# CONNECTEUR_2.net
KiCad netlist of a schematic drawn in Altium Designer
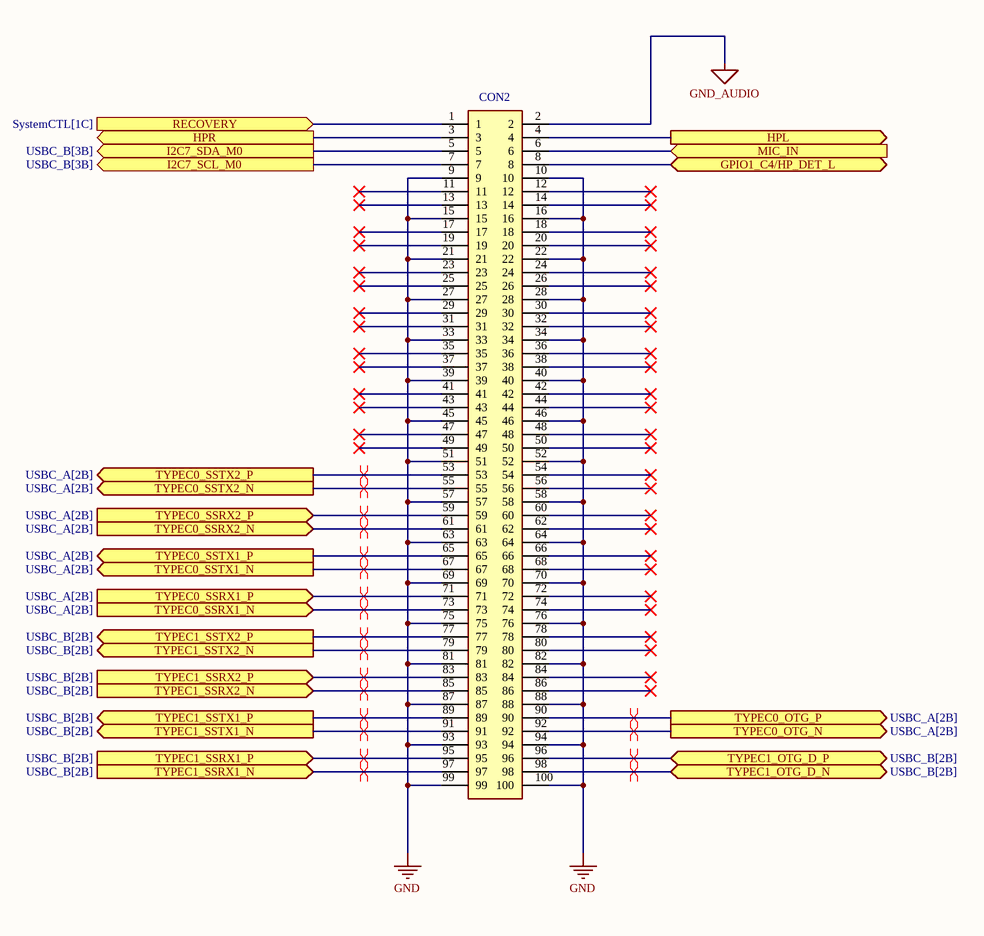
[diagram p0: CONNECTEUR_2.SchDoc, middle]

(export (version "E")
  (design (tool "Eeschema 10.0.6"))
  (components
    (comp (ref "CON2")
      (value "DF40HC")
      (footprint "SamacSys:DF40HC30100DS04V51")
      (description "Stacking Board Connector, DF40 Series, Receptacle, 0.4 mm, 100, Surface Mount, G")
      (fields
        (field (name "MANUFACTURER_PART_NUMBER") "DF40HC(3.0)-100DS-0.4V(51")
        (field (name "MOUSER PART NUMBER") "798-DF40HC30100DS451")
      )
      (libsource (lib "SamacSys") (part "DF40HC(3.0)-100DS-0.4V(51)"))
    )
  )
  (nets
    (net (code "1") (name "/GPIO1_C4{slash}HP_DET_L") (class "Default")
      (node (ref "CON2") (pin "8") (pinfunction "8_8") (pintype "passive"))
    )
    (net (code "2") (name "/HPL") (class "Default")
      (node (ref "CON2") (pin "4") (pinfunction "4_4") (pintype "passive"))
    )
    (net (code "3") (name "/HPR") (class "Default")
      (node (ref "CON2") (pin "3") (pinfunction "3_3") (pintype "passive"))
    )
    (net (code "4") (name "/I2C7_SCL_M0") (class "Default")
      (node (ref "CON2") (pin "7") (pinfunction "7_7") (pintype "passive"))
    )
    (net (code "5") (name "/I2C7_SDA_M0") (class "Default")
      (node (ref "CON2") (pin "5") (pinfunction "5_5") (pintype "passive"))
    )
    (net (code "6") (name "/MIC_IN") (class "Default")
      (node (ref "CON2") (pin "6") (pinfunction "6_6") (pintype "passive"))
    )
    (net (code "7") (name "/RECOVERY") (class "Default")
      (node (ref "CON2") (pin "1") (pinfunction "1_1") (pintype "passive"))
    )
    (net (code "8") (name "/TYPEC0_OTG_N") (class "Default")
      (node (ref "CON2") (pin "92") (pinfunction "92_92") (pintype "passive"))
    )
    (net (code "9") (name "/TYPEC0_OTG_P") (class "Default")
      (node (ref "CON2") (pin "90") (pinfunction "90_90") (pintype "passive"))
    )
    (net (code "10") (name "/TYPEC0_SSRX1_N") (class "Default")
      (node (ref "CON2") (pin "73") (pinfunction "73_73") (pintype "passive"))
    )
    (net (code "11") (name "/TYPEC0_SSRX1_P") (class "Default")
      (node (ref "CON2") (pin "71") (pinfunction "71_71") (pintype "passive"))
    )
    (net (code "12") (name "/TYPEC0_SSRX2_N") (class "Default")
      (node (ref "CON2") (pin "61") (pinfunction "61_61") (pintype "passive"))
    )
    (net (code "13") (name "/TYPEC0_SSRX2_P") (class "Default")
      (node (ref "CON2") (pin "59") (pinfunction "59_59") (pintype "passive"))
    )
    (net (code "14") (name "/TYPEC0_SSTX1_N") (class "Default")
      (node (ref "CON2") (pin "67") (pinfunction "67_67") (pintype "passive"))
    )
    (net (code "15") (name "/TYPEC0_SSTX1_P") (class "Default")
      (node (ref "CON2") (pin "65") (pinfunction "65_65") (pintype "passive"))
    )
    (net (code "16") (name "/TYPEC0_SSTX2_N") (class "Default")
      (node (ref "CON2") (pin "55") (pinfunction "55_55") (pintype "passive"))
    )
    (net (code "17") (name "/TYPEC0_SSTX2_P") (class "Default")
      (node (ref "CON2") (pin "53") (pinfunction "53_53") (pintype "passive"))
    )
    (net (code "18") (name "/TYPEC1_OTG_D_N") (class "Default")
      (node (ref "CON2") (pin "98") (pinfunction "98_98") (pintype "passive"))
    )
    (net (code "19") (name "/TYPEC1_OTG_D_P") (class "Default")
      (node (ref "CON2") (pin "96") (pinfunction "96_96") (pintype "passive"))
    )
    (net (code "20") (name "/TYPEC1_SSRX1_N") (class "Default")
      (node (ref "CON2") (pin "97") (pinfunction "97_97") (pintype "passive"))
    )
    (net (code "21") (name "/TYPEC1_SSRX1_P") (class "Default")
      (node (ref "CON2") (pin "95") (pinfunction "95_95") (pintype "passive"))
    )
    (net (code "22") (name "/TYPEC1_SSRX2_N") (class "Default")
      (node (ref "CON2") (pin "85") (pinfunction "85_85") (pintype "passive"))
    )
    (net (code "23") (name "/TYPEC1_SSRX2_P") (class "Default")
      (node (ref "CON2") (pin "83") (pinfunction "83_83") (pintype "passive"))
    )
    (net (code "24") (name "/TYPEC1_SSTX1_N") (class "Default")
      (node (ref "CON2") (pin "91") (pinfunction "91_91") (pintype "passive"))
    )
    (net (code "25") (name "/TYPEC1_SSTX1_P") (class "Default")
      (node (ref "CON2") (pin "89") (pinfunction "89_89") (pintype "passive"))
    )
    (net (code "26") (name "/TYPEC1_SSTX2_N") (class "Default")
      (node (ref "CON2") (pin "79") (pinfunction "79_79") (pintype "passive"))
    )
    (net (code "27") (name "/TYPEC1_SSTX2_P") (class "Default")
      (node (ref "CON2") (pin "77") (pinfunction "77_77") (pintype "passive"))
    )
    (net (code "28") (name "GND") (class "Default")
      (node (ref "CON2") (pin "10") (pinfunction "10_10") (pintype "passive"))
      (node (ref "CON2") (pin "100") (pinfunction "100_100") (pintype "passive"))
      (node (ref "CON2") (pin "15") (pinfunction "15_15") (pintype "passive"))
      (node (ref "CON2") (pin "16") (pinfunction "16_16") (pintype "passive"))
      (node (ref "CON2") (pin "21") (pinfunction "21_21") (pintype "passive"))
      (node (ref "CON2") (pin "22") (pinfunction "22_22") (pintype "passive"))
      (node (ref "CON2") (pin "27") (pinfunction "27_27") (pintype "passive"))
      (node (ref "CON2") (pin "28") (pinfunction "28_28") (pintype "passive"))
      (node (ref "CON2") (pin "33") (pinfunction "33_33") (pintype "passive"))
      (node (ref "CON2") (pin "34") (pinfunction "34_34") (pintype "passive"))
      (node (ref "CON2") (pin "39") (pinfunction "39_39") (pintype "passive"))
      (node (ref "CON2") (pin "40") (pinfunction "40_40") (pintype "passive"))
      (node (ref "CON2") (pin "45") (pinfunction "45_45") (pintype "passive"))
      (node (ref "CON2") (pin "46") (pinfunction "46_46") (pintype "passive"))
      (node (ref "CON2") (pin "51") (pinfunction "51_51") (pintype "passive"))
      (node (ref "CON2") (pin "52") (pinfunction "52_52") (pintype "passive"))
      (node (ref "CON2") (pin "57") (pinfunction "57_57") (pintype "passive"))
      (node (ref "CON2") (pin "58") (pinfunction "58_58") (pintype "passive"))
      (node (ref "CON2") (pin "63") (pinfunction "63_63") (pintype "passive"))
      (node (ref "CON2") (pin "64") (pinfunction "64_64") (pintype "passive"))
      (node (ref "CON2") (pin "69") (pinfunction "69_69") (pintype "passive"))
      (node (ref "CON2") (pin "70") (pinfunction "70_70") (pintype "passive"))
      (node (ref "CON2") (pin "75") (pinfunction "75_75") (pintype "passive"))
      (node (ref "CON2") (pin "76") (pinfunction "76_76") (pintype "passive"))
      (node (ref "CON2") (pin "81") (pinfunction "81_81") (pintype "passive"))
      (node (ref "CON2") (pin "82") (pinfunction "82_82") (pintype "passive"))
      (node (ref "CON2") (pin "87") (pinfunction "87_87") (pintype "passive"))
      (node (ref "CON2") (pin "88") (pinfunction "88_88") (pintype "passive"))
      (node (ref "CON2") (pin "9") (pinfunction "9_9") (pintype "passive"))
      (node (ref "CON2") (pin "93") (pinfunction "93_93") (pintype "passive"))
      (node (ref "CON2") (pin "94") (pinfunction "94_94") (pintype "passive"))
      (node (ref "CON2") (pin "99") (pinfunction "99_99") (pintype "passive"))
    )
    (net (code "29") (name "GND_AUDIO") (class "Default")
      (node (ref "CON2") (pin "2") (pinfunction "2_2") (pintype "passive"))
    )
    (net (code "30") (name "unconnected-(CON2-Pad11)") (class "Default")
      (node (ref "CON2") (pin "11") (pinfunction "11_11") (pintype "passive+no_connect"))
    )
    (net (code "31") (name "unconnected-(CON2-Pad12)") (class "Default")
      (node (ref "CON2") (pin "12") (pinfunction "12_12") (pintype "passive+no_connect"))
    )
    (net (code "32") (name "unconnected-(CON2-Pad13)") (class "Default")
      (node (ref "CON2") (pin "13") (pinfunction "13_13") (pintype "passive+no_connect"))
    )
    (net (code "33") (name "unconnected-(CON2-Pad14)") (class "Default")
      (node (ref "CON2") (pin "14") (pinfunction "14_14") (pintype "passive+no_connect"))
    )
    (net (code "34") (name "unconnected-(CON2-Pad17)") (class "Default")
      (node (ref "CON2") (pin "17") (pinfunction "17_17") (pintype "passive+no_connect"))
    )
    (net (code "35") (name "unconnected-(CON2-Pad18)") (class "Default")
      (node (ref "CON2") (pin "18") (pinfunction "18_18") (pintype "passive+no_connect"))
    )
    (net (code "36") (name "unconnected-(CON2-Pad19)") (class "Default")
      (node (ref "CON2") (pin "19") (pinfunction "19_19") (pintype "passive+no_connect"))
    )
    (net (code "37") (name "unconnected-(CON2-Pad20)") (class "Default")
      (node (ref "CON2") (pin "20") (pinfunction "20_20") (pintype "passive+no_connect"))
    )
    (net (code "38") (name "unconnected-(CON2-Pad23)") (class "Default")
      (node (ref "CON2") (pin "23") (pinfunction "23_23") (pintype "passive+no_connect"))
    )
    (net (code "39") (name "unconnected-(CON2-Pad24)") (class "Default")
      (node (ref "CON2") (pin "24") (pinfunction "24_24") (pintype "passive+no_connect"))
    )
    (net (code "40") (name "unconnected-(CON2-Pad25)") (class "Default")
      (node (ref "CON2") (pin "25") (pinfunction "25_25") (pintype "passive+no_connect"))
    )
    (net (code "41") (name "unconnected-(CON2-Pad26)") (class "Default")
      (node (ref "CON2") (pin "26") (pinfunction "26_26") (pintype "passive+no_connect"))
    )
    (net (code "42") (name "unconnected-(CON2-Pad29)") (class "Default")
      (node (ref "CON2") (pin "29") (pinfunction "29_29") (pintype "passive+no_connect"))
    )
    (net (code "43") (name "unconnected-(CON2-Pad30)") (class "Default")
      (node (ref "CON2") (pin "30") (pinfunction "30_30") (pintype "passive+no_connect"))
    )
    (net (code "44") (name "unconnected-(CON2-Pad31)") (class "Default")
      (node (ref "CON2") (pin "31") (pinfunction "31_31") (pintype "passive+no_connect"))
    )
    (net (code "45") (name "unconnected-(CON2-Pad32)") (class "Default")
      (node (ref "CON2") (pin "32") (pinfunction "32_32") (pintype "passive+no_connect"))
    )
    (net (code "46") (name "unconnected-(CON2-Pad35)") (class "Default")
      (node (ref "CON2") (pin "35") (pinfunction "35_35") (pintype "passive+no_connect"))
    )
    (net (code "47") (name "unconnected-(CON2-Pad36)") (class "Default")
      (node (ref "CON2") (pin "36") (pinfunction "36_36") (pintype "passive+no_connect"))
    )
    (net (code "48") (name "unconnected-(CON2-Pad37)") (class "Default")
      (node (ref "CON2") (pin "37") (pinfunction "37_37") (pintype "passive+no_connect"))
    )
    (net (code "49") (name "unconnected-(CON2-Pad38)") (class "Default")
      (node (ref "CON2") (pin "38") (pinfunction "38_38") (pintype "passive+no_connect"))
    )
    (net (code "50") (name "unconnected-(CON2-Pad41)") (class "Default")
      (node (ref "CON2") (pin "41") (pinfunction "41_41") (pintype "passive+no_connect"))
    )
    (net (code "51") (name "unconnected-(CON2-Pad42)") (class "Default")
      (node (ref "CON2") (pin "42") (pinfunction "42_42") (pintype "passive+no_connect"))
    )
    (net (code "52") (name "unconnected-(CON2-Pad43)") (class "Default")
      (node (ref "CON2") (pin "43") (pinfunction "43_43") (pintype "passive+no_connect"))
    )
    (net (code "53") (name "unconnected-(CON2-Pad44)") (class "Default")
      (node (ref "CON2") (pin "44") (pinfunction "44_44") (pintype "passive+no_connect"))
    )
    (net (code "54") (name "unconnected-(CON2-Pad47)") (class "Default")
      (node (ref "CON2") (pin "47") (pinfunction "47_47") (pintype "passive+no_connect"))
    )
    (net (code "55") (name "unconnected-(CON2-Pad48)") (class "Default")
      (node (ref "CON2") (pin "48") (pinfunction "48_48") (pintype "passive+no_connect"))
    )
    (net (code "56") (name "unconnected-(CON2-Pad49)") (class "Default")
      (node (ref "CON2") (pin "49") (pinfunction "49_49") (pintype "passive+no_connect"))
    )
    (net (code "57") (name "unconnected-(CON2-Pad50)") (class "Default")
      (node (ref "CON2") (pin "50") (pinfunction "50_50") (pintype "passive+no_connect"))
    )
    (net (code "58") (name "unconnected-(CON2-Pad54)") (class "Default")
      (node (ref "CON2") (pin "54") (pinfunction "54_54") (pintype "passive+no_connect"))
    )
    (net (code "59") (name "unconnected-(CON2-Pad56)") (class "Default")
      (node (ref "CON2") (pin "56") (pinfunction "56_56") (pintype "passive+no_connect"))
    )
    (net (code "60") (name "unconnected-(CON2-Pad60)") (class "Default")
      (node (ref "CON2") (pin "60") (pinfunction "60_60") (pintype "passive+no_connect"))
    )
    (net (code "61") (name "unconnected-(CON2-Pad62)") (class "Default")
      (node (ref "CON2") (pin "62") (pinfunction "62_62") (pintype "passive+no_connect"))
    )
    (net (code "62") (name "unconnected-(CON2-Pad66)") (class "Default")
      (node (ref "CON2") (pin "66") (pinfunction "66_66") (pintype "passive+no_connect"))
    )
    (net (code "63") (name "unconnected-(CON2-Pad68)") (class "Default")
      (node (ref "CON2") (pin "68") (pinfunction "68_68") (pintype "passive+no_connect"))
    )
    (net (code "64") (name "unconnected-(CON2-Pad72)") (class "Default")
      (node (ref "CON2") (pin "72") (pinfunction "72_72") (pintype "passive+no_connect"))
    )
    (net (code "65") (name "unconnected-(CON2-Pad74)") (class "Default")
      (node (ref "CON2") (pin "74") (pinfunction "74_74") (pintype "passive+no_connect"))
    )
    (net (code "66") (name "unconnected-(CON2-Pad78)") (class "Default")
      (node (ref "CON2") (pin "78") (pinfunction "78_78") (pintype "passive+no_connect"))
    )
    (net (code "67") (name "unconnected-(CON2-Pad80)") (class "Default")
      (node (ref "CON2") (pin "80") (pinfunction "80_80") (pintype "passive+no_connect"))
    )
    (net (code "68") (name "unconnected-(CON2-Pad84)") (class "Default")
      (node (ref "CON2") (pin "84") (pinfunction "84_84") (pintype "passive+no_connect"))
    )
    (net (code "69") (name "unconnected-(CON2-Pad86)") (class "Default")
      (node (ref "CON2") (pin "86") (pinfunction "86_86") (pintype "passive+no_connect"))
    )
  )
)
